# SEGplug.net
KiCad netlist of a schematic drawn in EAGLE
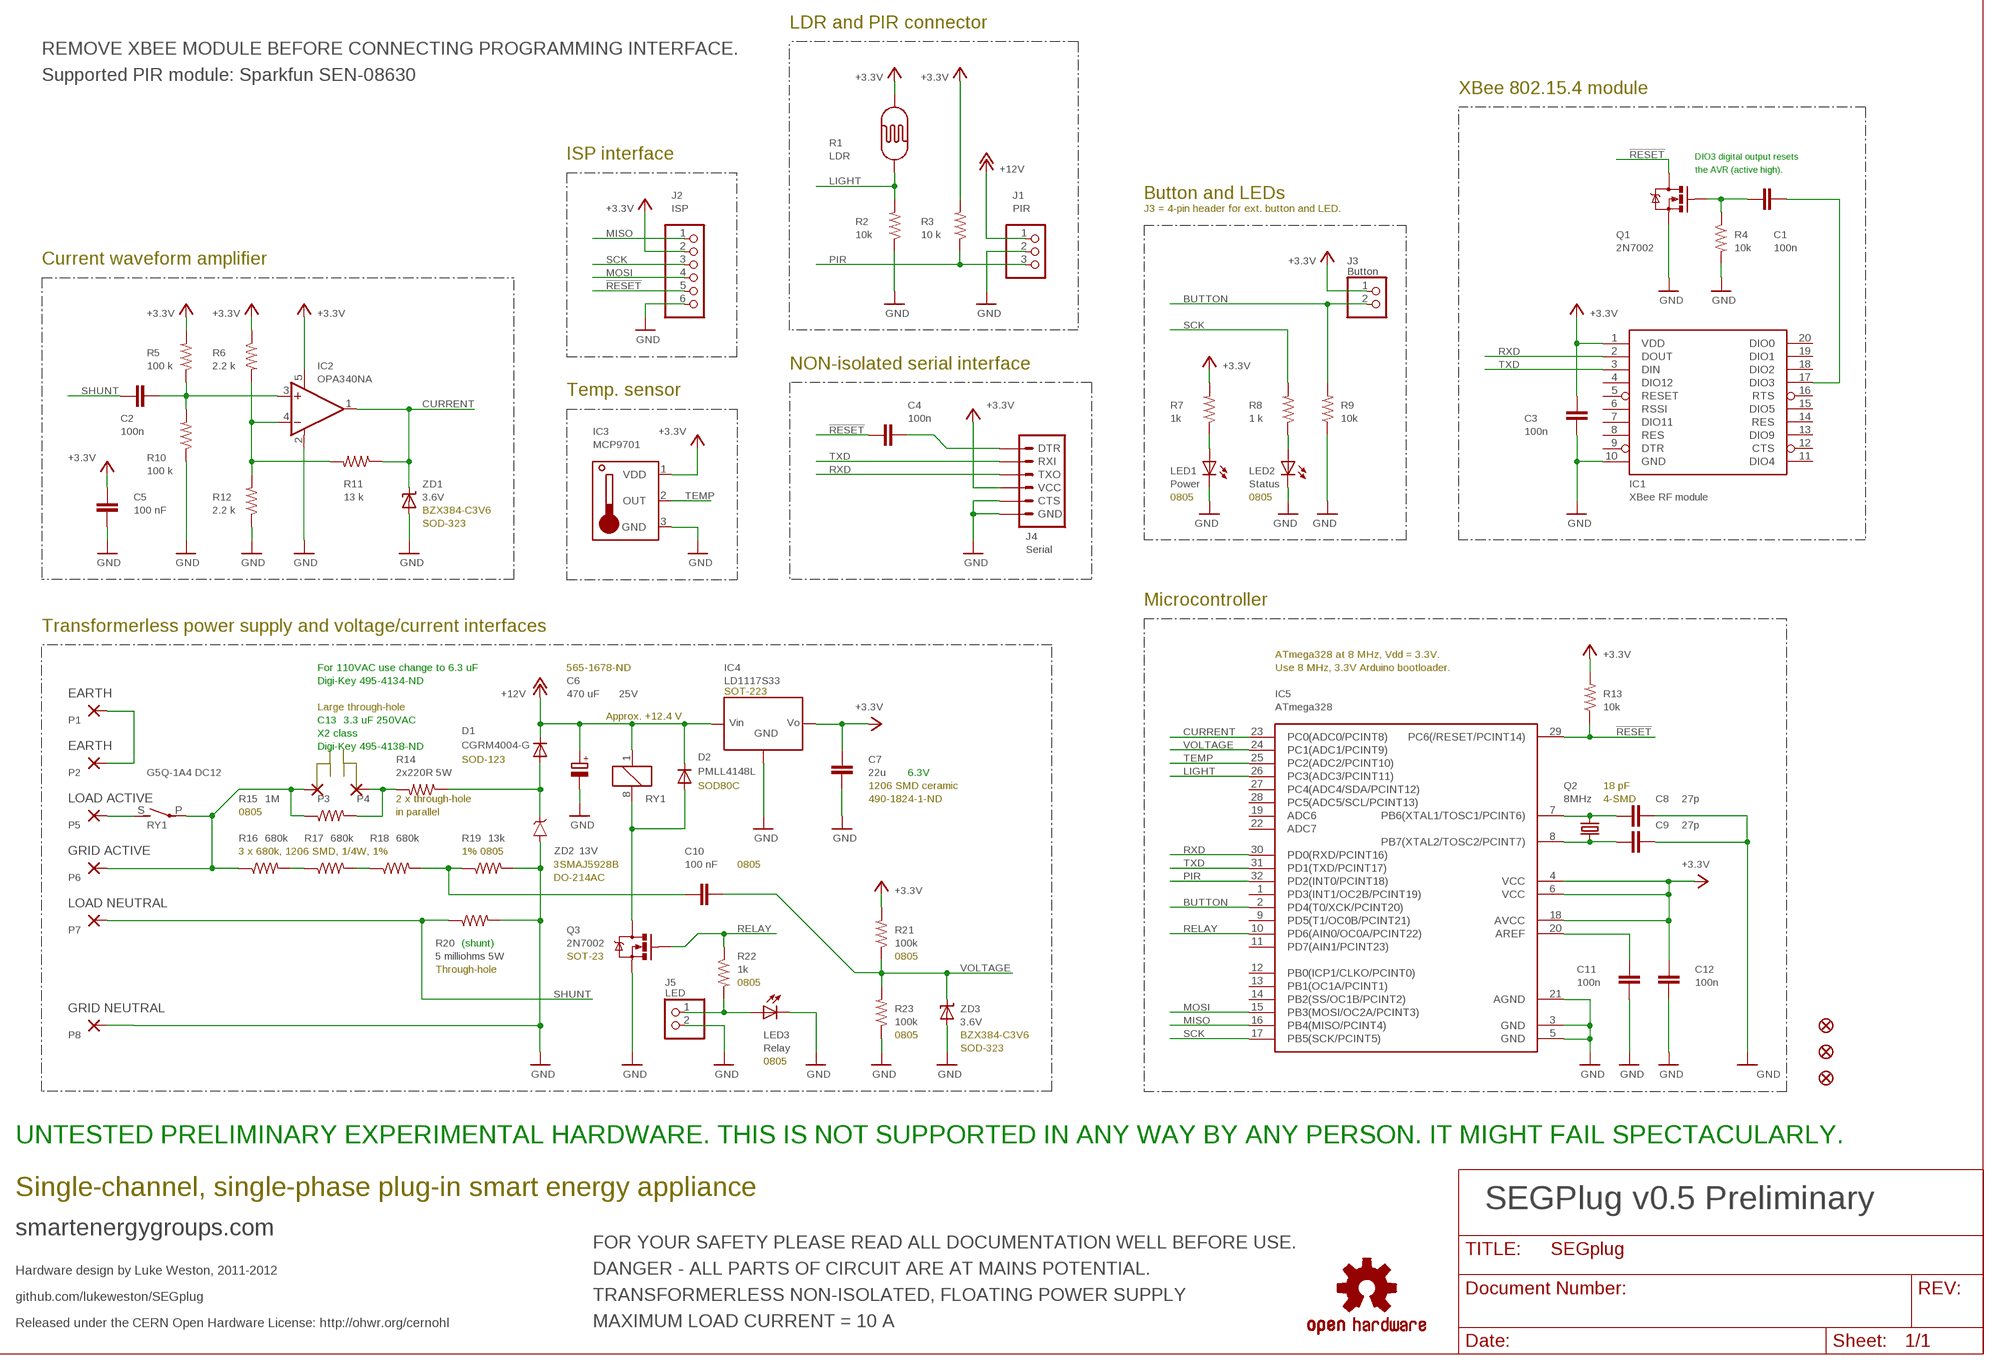
[diagram p0: schematic, sheet 1, part 1 of 2]
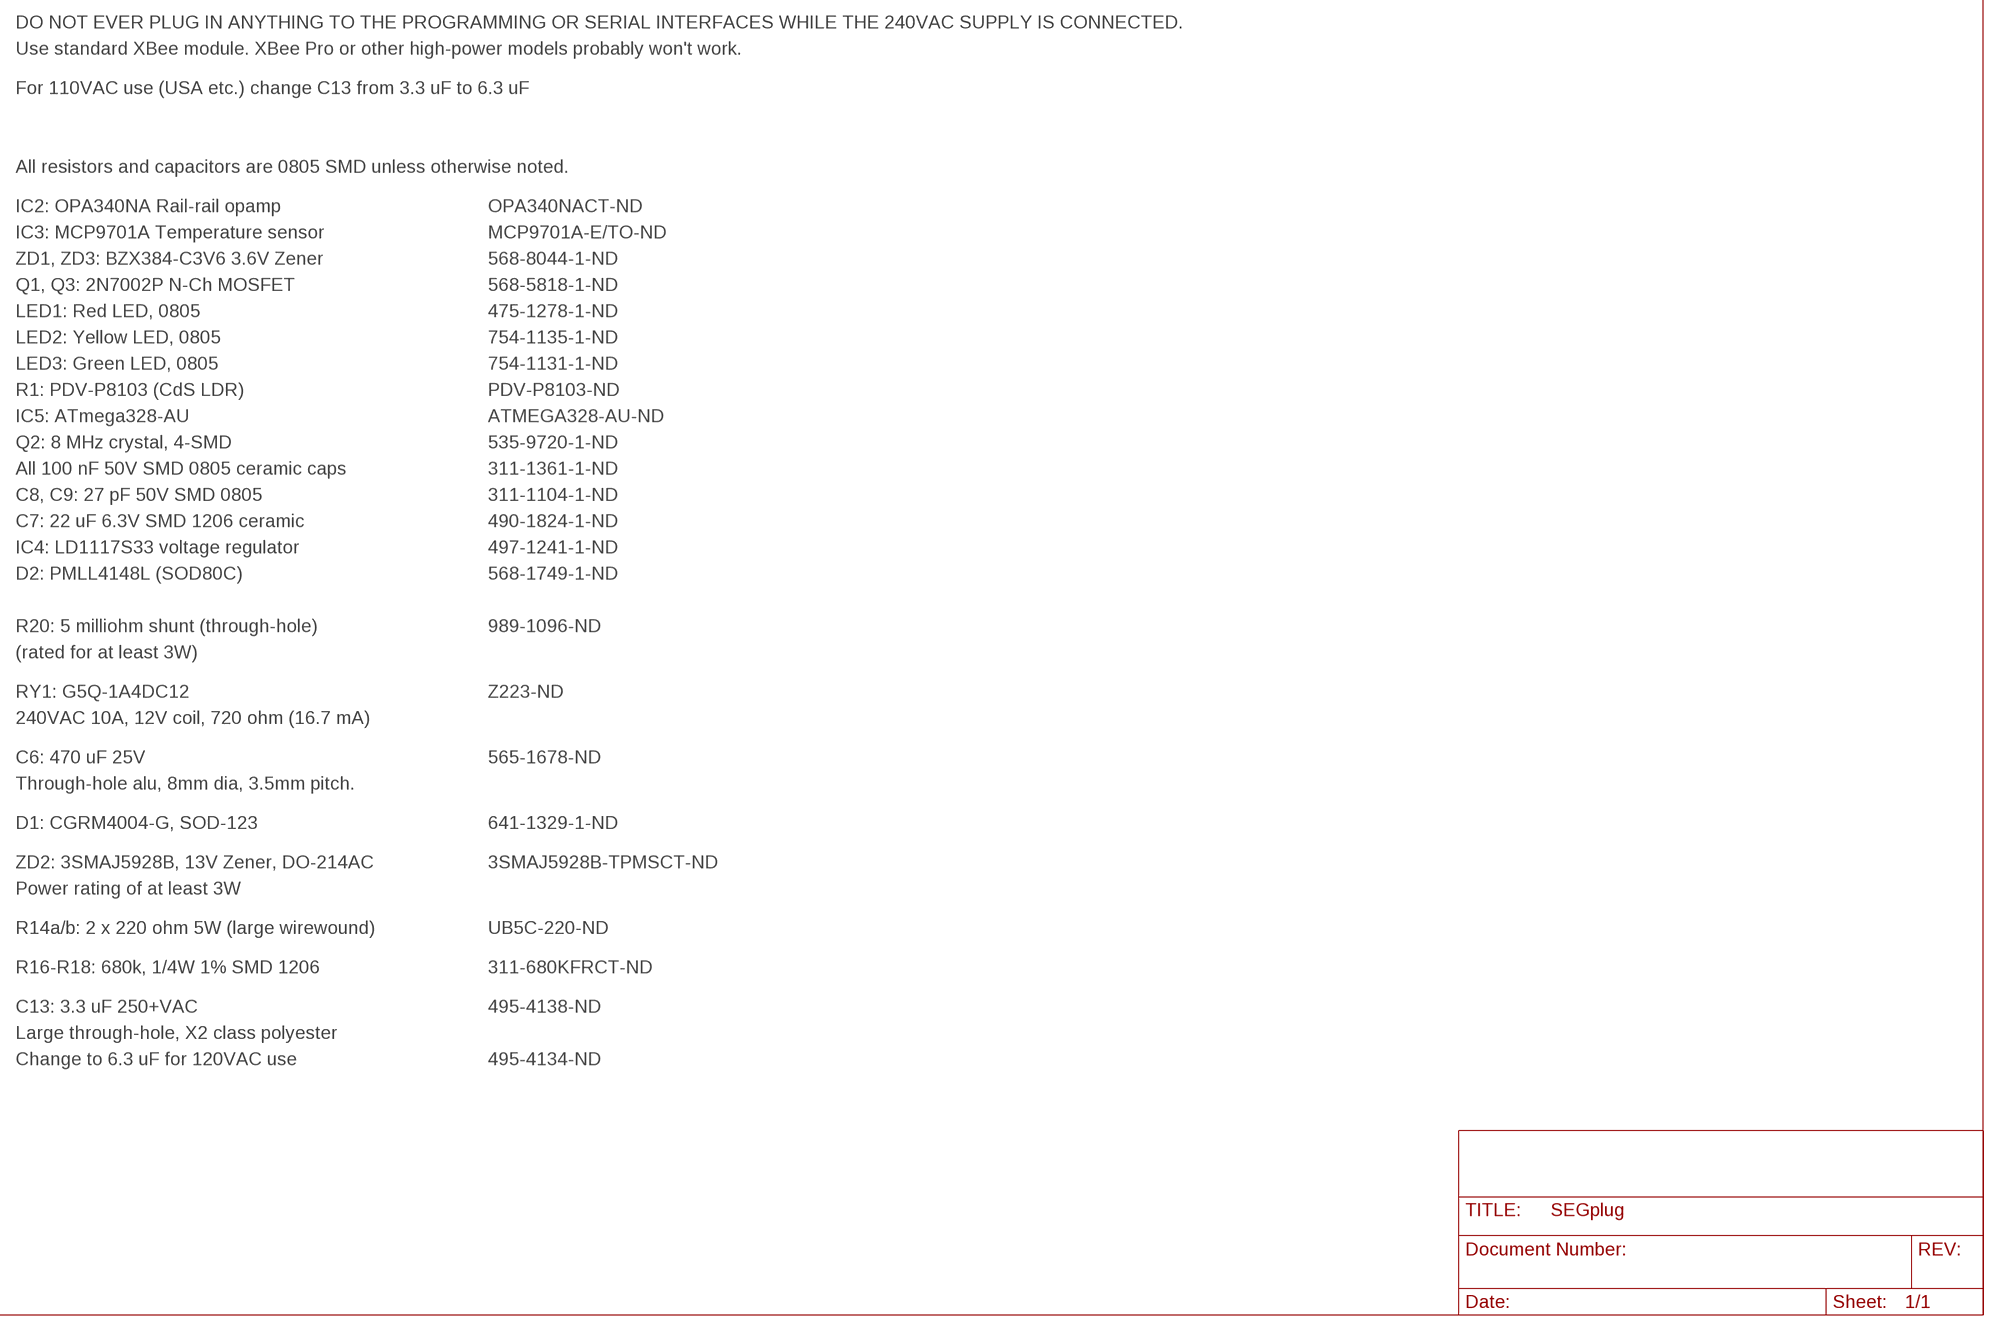
[diagram p1: schematic, sheet 1, part 2 of 2]

(export (version "E")
  (design (tool "Eeschema 10.0.6"))
  (components
    (comp (ref "C1")
      (value "100n")
      (footprint "eagle-import:C0805K")
      (libsource (lib "eagle-import") (part "C-EUC0805K"))
    )
    (comp (ref "C2")
      (value "100n")
      (footprint "eagle-import:C0805K")
      (libsource (lib "eagle-import") (part "C-EUC0805K"))
    )
    (comp (ref "C3")
      (value "100n")
      (footprint "eagle-import:C0805K")
      (libsource (lib "eagle-import") (part "C-EUC0805K"))
    )
    (comp (ref "C4")
      (value "100n")
      (footprint "eagle-import:C0805K")
      (libsource (lib "eagle-import") (part "C-EUC0805K"))
    )
    (comp (ref "C5")
      (value "100 nF")
      (footprint "eagle-import:C0805K")
      (libsource (lib "eagle-import") (part "C-EUC0805K"))
    )
    (comp (ref "C6")
      (value "470 uF")
      (footprint "eagle-import:E3,5-8")
      (libsource (lib "eagle-import") (part "CPOL-EUE3.5-8"))
    )
    (comp (ref "C7")
      (value "22u")
      (footprint "eagle-import:C1206K")
      (libsource (lib "eagle-import") (part "C-EUC1206K"))
    )
    (comp (ref "C8")
      (value "27p")
      (footprint "eagle-import:C0805K")
      (libsource (lib "eagle-import") (part "C-EUC0805K"))
    )
    (comp (ref "C9")
      (value "27p")
      (footprint "eagle-import:C0805K")
      (libsource (lib "eagle-import") (part "C-EUC0805K"))
    )
    (comp (ref "C10")
      (value "100 nF")
      (footprint "eagle-import:C0805K")
      (libsource (lib "eagle-import") (part "C-EUC0805K"))
    )
    (comp (ref "C11")
      (value "100n")
      (footprint "eagle-import:C0805K")
      (libsource (lib "eagle-import") (part "C-EUC0805K"))
    )
    (comp (ref "C12")
      (value "100n")
      (footprint "eagle-import:C0805K")
      (libsource (lib "eagle-import") (part "C-EUC0805K"))
    )
    (comp (ref "D1")
      (value "CGRM4004-G")
      (footprint "eagle-import:SOD-123_MINI-SMA")
      (libsource (lib "eagle-import") (part "CGRM400-G4"))
    )
    (comp (ref "D2")
      (value "PMLL4148L")
      (footprint "eagle-import:MINIMELF")
      (libsource (lib "eagle-import") (part "DIODE-MINIMELF"))
    )
    (comp (ref "IC1")
      (value "XBee RF module")
      (footprint "eagle-import:XBEE-SMD")
      (libsource (lib "eagle-import") (part "XBEE-1B3"))
    )
    (comp (ref "IC2")
      (value "OPA340NA")
      (footprint "eagle-import:SOT23-5")
      (fields (field (name "MPN") "OPA336NA"))
      (libsource (lib "eagle-import") (part "OPA336N"))
    )
    (comp (ref "IC3")
      (value "MCP9701")
      (footprint "eagle-import:TO92")
      (libsource (lib "eagle-import") (part "MCP9700"))
    )
    (comp (ref "IC4")
      (value "LD1117S33")
      (footprint "eagle-import:SOT223")
      (fields (field (name "MPN") "REG1117"))
      (libsource (lib "eagle-import") (part "REG1117"))
    )
    (comp (ref "IC5")
      (value "ATmega328")
      (footprint "eagle-import:TQFP32-08")
      (libsource (lib "eagle-import") (part "MEGA48/88/168-AU"))
    )
    (comp (ref "J1")
      (value "PIR")
      (footprint "eagle-import:1X03")
      (libsource (lib "eagle-import") (part "PINHD-1X3"))
    )
    (comp (ref "J2")
      (value "ISP")
      (footprint "eagle-import:1X06")
      (libsource (lib "eagle-import") (part "PINHD-1X6"))
    )
    (comp (ref "J3")
      (value "Button")
      (footprint "eagle-import:1X02")
      (libsource (lib "eagle-import") (part "PINHD-1X2"))
    )
    (comp (ref "J4")
      (value "Serial")
      (footprint "eagle-import:1X06")
      (libsource (lib "eagle-import") (part "ARDUINO_SERIAL_PROGRAMPTH"))
    )
    (comp (ref "J5")
      (value "LED")
      (footprint "eagle-import:1X02")
      (libsource (lib "eagle-import") (part "PINHD-1X2"))
    )
    (comp (ref "JP1")
      (value "FIDUCIAL1X2")
      (footprint "eagle-import:FIDUCIAL-1X2")
      (libsource (lib "eagle-import") (part "FIDUCIAL1X2"))
    )
    (comp (ref "JP2")
      (value "FIDUCIAL1X2")
      (footprint "eagle-import:FIDUCIAL-1X2")
      (libsource (lib "eagle-import") (part "FIDUCIAL1X2"))
    )
    (comp (ref "JP3")
      (value "FIDUCIAL1X2")
      (footprint "eagle-import:FIDUCIAL-1X2")
      (libsource (lib "eagle-import") (part "FIDUCIAL1X2"))
    )
    (comp (ref "LED1")
      (value "Power")
      (footprint "eagle-import:CHIPLED_0805")
      (libsource (lib "eagle-import") (part "LEDCHIPLED_0805"))
    )
    (comp (ref "LED2")
      (value "Status")
      (footprint "eagle-import:CHIPLED_0805")
      (libsource (lib "eagle-import") (part "LEDCHIPLED_0805"))
    )
    (comp (ref "LED3")
      (value "Relay")
      (footprint "eagle-import:CHIPLED_0805")
      (libsource (lib "eagle-import") (part "LEDCHIPLED_0805"))
    )
    (comp (ref "P1")
      (value "EARTH")
      (footprint "eagle-import:4,16O1,6")
      (libsource (lib "eagle-import") (part "WIREPAD4,16O1,6"))
    )
    (comp (ref "P2")
      (value "EARTH")
      (footprint "eagle-import:4,16O1,6")
      (libsource (lib "eagle-import") (part "WIREPAD4,16O1,6"))
    )
    (comp (ref "P3")
      (value "CAP")
      (footprint "eagle-import:4,16O1,6")
      (libsource (lib "eagle-import") (part "WIREPAD4,16O1,6"))
    )
    (comp (ref "P4")
      (value "CAP")
      (footprint "eagle-import:4,16O1,6")
      (libsource (lib "eagle-import") (part "WIREPAD4,16O1,6"))
    )
    (comp (ref "P5")
      (value "LOAD ACTIVE")
      (footprint "eagle-import:4,16O1,6")
      (libsource (lib "eagle-import") (part "WIREPAD4,16O1,6"))
    )
    (comp (ref "P6")
      (value "GRID ACTIVE")
      (footprint "eagle-import:4,16O1,6")
      (libsource (lib "eagle-import") (part "WIREPAD4,16O1,6"))
    )
    (comp (ref "P7")
      (value "LOAD NEUTRAL")
      (footprint "eagle-import:4,16O1,6")
      (libsource (lib "eagle-import") (part "WIREPAD4,16O1,6"))
    )
    (comp (ref "P8")
      (value "GRID NEUTRAL")
      (footprint "eagle-import:4,16O1,6")
      (libsource (lib "eagle-import") (part "WIREPAD4,16O1,6"))
    )
    (comp (ref "Q1")
      (value "2N7002")
      (footprint "eagle-import:SOT23-3")
      (libsource (lib "eagle-import") (part "MOSFET-NCHANNELSMD"))
    )
    (comp (ref "Q2")
      (value "8MHz")
      (footprint "eagle-import:CRYSTAL-SMD-5X3")
      (libsource (lib "eagle-import") (part "CRYSTAL5X3"))
    )
    (comp (ref "Q3")
      (value "2N7002")
      (footprint "eagle-import:SOT23-3")
      (libsource (lib "eagle-import") (part "MOSFET-NCHANNELSMD"))
    )
    (comp (ref "R1")
      (value "LDR")
      (footprint "eagle-import:PHOTOCELL")
      (libsource (lib "eagle-import") (part "PHOTOCELLPTH"))
    )
    (comp (ref "R2")
      (value "10k")
      (footprint "eagle-import:M0805")
      (libsource (lib "eagle-import") (part "resistor_R-US_M0805"))
    )
    (comp (ref "R3")
      (value "10 k")
      (footprint "eagle-import:M0805")
      (libsource (lib "eagle-import") (part "resistor_R-US_M0805"))
    )
    (comp (ref "R4")
      (value "10k")
      (footprint "eagle-import:M0805")
      (libsource (lib "eagle-import") (part "resistor_R-US_M0805"))
    )
    (comp (ref "R5")
      (value "100 k")
      (footprint "eagle-import:M0805")
      (libsource (lib "eagle-import") (part "resistor_R-US_M0805"))
    )
    (comp (ref "R6")
      (value "2.2 k")
      (footprint "eagle-import:M0805")
      (libsource (lib "eagle-import") (part "resistor_R-US_M0805"))
    )
    (comp (ref "R7")
      (value "1k")
      (footprint "eagle-import:M0805")
      (libsource (lib "eagle-import") (part "resistor_R-US_M0805"))
    )
    (comp (ref "R8")
      (value "1 k")
      (footprint "eagle-import:M0805")
      (libsource (lib "eagle-import") (part "resistor_R-US_M0805"))
    )
    (comp (ref "R9")
      (value "10k")
      (footprint "eagle-import:M0805")
      (libsource (lib "eagle-import") (part "resistor_R-US_M0805"))
    )
    (comp (ref "R10")
      (value "100 k")
      (footprint "eagle-import:M0805")
      (libsource (lib "eagle-import") (part "resistor_R-US_M0805"))
    )
    (comp (ref "R11")
      (value "13 k")
      (footprint "eagle-import:M0805")
      (libsource (lib "eagle-import") (part "resistor_R-US_M0805"))
    )
    (comp (ref "R12")
      (value "2.2 k")
      (footprint "eagle-import:M0805")
      (libsource (lib "eagle-import") (part "resistor_R-US_M0805"))
    )
    (comp (ref "R13")
      (value "10k")
      (footprint "eagle-import:M0805")
      (libsource (lib "eagle-import") (part "resistor_R-US_M0805"))
    )
    (comp (ref "R14")
      (value "2x220R 5W")
      (footprint "eagle-import:0617_17")
      (libsource (lib "eagle-import") (part "R-US_0617/17"))
    )
    (comp (ref "R15")
      (value "1M")
      (footprint "eagle-import:M0805")
      (libsource (lib "eagle-import") (part "R-US_M0805"))
    )
    (comp (ref "R16")
      (value "680k")
      (footprint "eagle-import:M1206")
      (libsource (lib "eagle-import") (part "R-US_M1206"))
    )
    (comp (ref "R17")
      (value "680k")
      (footprint "eagle-import:M1206")
      (libsource (lib "eagle-import") (part "R-US_M1206"))
    )
    (comp (ref "R18")
      (value "680k")
      (footprint "eagle-import:M1206")
      (libsource (lib "eagle-import") (part "R-US_M1206"))
    )
    (comp (ref "R19")
      (value "13k")
      (footprint "eagle-import:M0805")
      (libsource (lib "eagle-import") (part "resistor_R-US_M0805"))
    )
    (comp (ref "R20")
      (value "5 milliohms 5W")
      (footprint "eagle-import:RSENSE2_RSENSE")
      (libsource (lib "eagle-import") (part "RSENSE2_RSENSE"))
    )
    (comp (ref "R21")
      (value "100k")
      (footprint "eagle-import:M0805")
      (libsource (lib "eagle-import") (part "resistor_R-US_M0805"))
    )
    (comp (ref "R22")
      (value "1k")
      (footprint "eagle-import:M0805")
      (libsource (lib "eagle-import") (part "resistor_R-US_M0805"))
    )
    (comp (ref "R23")
      (value "100k")
      (footprint "eagle-import:M0805")
      (libsource (lib "eagle-import") (part "resistor_R-US_M0805"))
    )
    (comp (ref "RY1")
      (value "G5Q-1A4 DC12")
      (footprint "eagle-import:G6C-1117P")
      (libsource (lib "eagle-import") (part "G6C-1117P"))
    )
    (comp (ref "U$")
      (value "OSHW-LOGOS")
      (footprint "eagle-import:OSHW-LOGO-S")
      (libsource (lib "eagle-import") (part "OSHW-LOGOS"))
    )
    (comp (ref "ZD1")
      (value "3.6V")
      (footprint "eagle-import:SOD-323")
      (libsource (lib "eagle-import") (part "DIODE-ZENER-BZT52"))
    )
    (comp (ref "ZD2")
      (value "13V")
      (footprint "eagle-import:DO214AC")
      (libsource (lib "eagle-import") (part "ZENER"))
    )
    (comp (ref "ZD3")
      (value "3.6V")
      (footprint "eagle-import:SOD-323")
      (libsource (lib "eagle-import") (part "DIODE-ZENER-BZT52"))
    )
  )
  (nets
    (net (code "1") (name "+3.3V") (class "Default")
      (node (ref "C12") (pin "1") (pinfunction "1_1") (pintype "passive"))
      (node (ref "C3") (pin "1") (pinfunction "1_1") (pintype "passive"))
      (node (ref "C5") (pin "1") (pinfunction "1_1") (pintype "passive"))
      (node (ref "C7") (pin "1") (pinfunction "1_1") (pintype "passive"))
      (node (ref "IC1") (pin "1") (pinfunction "VDD_1") (pintype "power_in"))
      (node (ref "IC2") (pin "5") (pinfunction "V+_5") (pintype "power_in"))
      (node (ref "IC3") (pin "1") (pinfunction "VDD_1") (pintype "power_in"))
      (node (ref "IC4") (pin "2") (pinfunction "VOUT_2") (pintype "power_in"))
      (node (ref "IC5") (pin "18") (pinfunction "AVCC_18") (pintype "passive"))
      (node (ref "IC5") (pin "4") (pinfunction "VCC_4") (pintype "power_in"))
      (node (ref "IC5") (pin "6") (pinfunction "VCC_6") (pintype "power_in"))
      (node (ref "J2") (pin "2") (pinfunction "2_2") (pintype "passive"))
      (node (ref "J3") (pin "1") (pinfunction "1_1") (pintype "passive"))
      (node (ref "J4") (pin "4") (pinfunction "VCC_4") (pintype "passive"))
      (node (ref "R1") (pin "2") (pinfunction "P$2_2") (pintype "bidirectional"))
      (node (ref "R13") (pin "2") (pinfunction "2_2") (pintype "passive"))
      (node (ref "R21") (pin "2") (pinfunction "2_2") (pintype "passive"))
      (node (ref "R3") (pin "2") (pinfunction "2_2") (pintype "passive"))
      (node (ref "R5") (pin "2") (pinfunction "2_2") (pintype "passive"))
      (node (ref "R6") (pin "1") (pinfunction "1_1") (pintype "passive"))
      (node (ref "R7") (pin "2") (pinfunction "2_2") (pintype "passive"))
    )
    (net (code "2") (name "+12V") (class "Default")
      (node (ref "C6") (pin "+") (pinfunction "+_+") (pintype "passive"))
      (node (ref "D1") (pin "C") (pinfunction "C_C") (pintype "passive"))
      (node (ref "D2") (pin "C") (pinfunction "C_C") (pintype "passive"))
      (node (ref "IC4") (pin "3") (pinfunction "VIN_3") (pintype "power_in"))
      (node (ref "J1") (pin "1") (pinfunction "1_1") (pintype "passive"))
      (node (ref "RY1") (pin "1") (pinfunction "1_1") (pintype "passive"))
    )
    (net (code "3") (name "/BUTTON") (class "Default")
      (node (ref "IC5") (pin "2") (pinfunction "PD4(T0/XCK/PCINT20)_2") (pintype "bidirectional"))
      (node (ref "J3") (pin "2") (pinfunction "2_2") (pintype "passive"))
      (node (ref "R9") (pin "2") (pinfunction "2_2") (pintype "passive"))
    )
    (net (code "4") (name "/CURRENT") (class "Default")
      (node (ref "IC2") (pin "1") (pinfunction "OUT_1") (pintype "output"))
      (node (ref "IC5") (pin "23") (pinfunction "PC0(ADC0/PCINT8)_23") (pintype "bidirectional"))
      (node (ref "R11") (pin "1") (pinfunction "1_1") (pintype "passive"))
      (node (ref "ZD1") (pin "1") (pinfunction "C_1") (pintype "passive"))
    )
    (net (code "5") (name "/LIGHT") (class "Default")
      (node (ref "IC5") (pin "26") (pinfunction "PC3(ADC3/PCINT11)_26") (pintype "bidirectional"))
      (node (ref "R1") (pin "1") (pinfunction "P$1_1") (pintype "bidirectional"))
      (node (ref "R2") (pin "2") (pinfunction "2_2") (pintype "passive"))
    )
    (net (code "6") (name "/MISO") (class "Default")
      (node (ref "IC5") (pin "16") (pinfunction "PB4(MISO/PCINT4)_16") (pintype "bidirectional"))
      (node (ref "J2") (pin "1") (pinfunction "1_1") (pintype "passive"))
    )
    (net (code "7") (name "/MOSI") (class "Default")
      (node (ref "IC5") (pin "15") (pinfunction "PB3(MOSI/OC2A/PCINT3)_15") (pintype "bidirectional"))
      (node (ref "J2") (pin "4") (pinfunction "4_4") (pintype "passive"))
    )
    (net (code "8") (name "/PIR") (class "Default")
      (node (ref "IC5") (pin "32") (pinfunction "PD2(INT0/PCINT18)_32") (pintype "bidirectional"))
      (node (ref "J1") (pin "3") (pinfunction "3_3") (pintype "passive"))
      (node (ref "R3") (pin "1") (pinfunction "1_1") (pintype "passive"))
    )
    (net (code "9") (name "/RELAY") (class "Default")
      (node (ref "IC5") (pin "10") (pinfunction "PD6(AIN0/OC0A/PCINT22)_10") (pintype "bidirectional"))
      (node (ref "Q3") (pin "1") (pinfunction "G_1") (pintype "passive"))
      (node (ref "R22") (pin "1") (pinfunction "1_1") (pintype "passive"))
    )
    (net (code "10") (name "/RXD") (class "Default")
      (node (ref "IC1") (pin "2") (pinfunction "DOUT_2") (pintype "output"))
      (node (ref "IC5") (pin "30") (pinfunction "PD0(RXD/PCINT16)_30") (pintype "bidirectional"))
      (node (ref "J4") (pin "3") (pinfunction "TXO_3") (pintype "passive"))
    )
    (net (code "11") (name "/SCK") (class "Default")
      (node (ref "IC5") (pin "17") (pinfunction "PB5(SCK/PCINT5)_17") (pintype "bidirectional"))
      (node (ref "J2") (pin "3") (pinfunction "3_3") (pintype "passive"))
      (node (ref "R8") (pin "2") (pinfunction "2_2") (pintype "passive"))
    )
    (net (code "12") (name "/SHUNT") (class "Default")
      (node (ref "C2") (pin "2") (pinfunction "2_2") (pintype "passive"))
      (node (ref "P7") (pin "1") (pinfunction "P_1") (pintype "passive"))
      (node (ref "R20") (pin "P$1") (pinfunction "1_P$1") (pintype "passive"))
    )
    (net (code "13") (name "/TEMP") (class "Default")
      (node (ref "IC3") (pin "2") (pinfunction "OUT_2") (pintype "output"))
      (node (ref "IC5") (pin "25") (pinfunction "PC2(ADC2/PCINT10)_25") (pintype "bidirectional"))
    )
    (net (code "14") (name "/TXD") (class "Default")
      (node (ref "IC1") (pin "3") (pinfunction "DIN_3") (pintype "input"))
      (node (ref "IC5") (pin "31") (pinfunction "PD1(TXD/PCINT17)_31") (pintype "bidirectional"))
      (node (ref "J4") (pin "2") (pinfunction "RXI_2") (pintype "passive"))
    )
    (net (code "15") (name "/VOLTAGE") (class "Default")
      (node (ref "C10") (pin "1") (pinfunction "1_1") (pintype "passive"))
      (node (ref "IC5") (pin "24") (pinfunction "PC1(ADC1/PCINT9)_24") (pintype "bidirectional"))
      (node (ref "R21") (pin "1") (pinfunction "1_1") (pintype "passive"))
      (node (ref "R23") (pin "2") (pinfunction "2_2") (pintype "passive"))
      (node (ref "ZD3") (pin "1") (pinfunction "C_1") (pintype "passive"))
    )
    (net (code "16") (name "/~{RESET}") (class "Default")
      (node (ref "C4") (pin "2") (pinfunction "2_2") (pintype "passive"))
      (node (ref "IC5") (pin "29") (pinfunction "PC6(/RESET/PCINT14)_29") (pintype "bidirectional"))
      (node (ref "J2") (pin "5") (pinfunction "5_5") (pintype "passive"))
      (node (ref "Q1") (pin "3") (pinfunction "D_3") (pintype "passive"))
      (node (ref "R13") (pin "1") (pinfunction "1_1") (pintype "passive"))
    )
    (net (code "17") (name "GND") (class "Default")
      (node (ref "C11") (pin "2") (pinfunction "2_2") (pintype "passive"))
      (node (ref "C12") (pin "2") (pinfunction "2_2") (pintype "passive"))
      (node (ref "C3") (pin "2") (pinfunction "2_2") (pintype "passive"))
      (node (ref "C5") (pin "2") (pinfunction "2_2") (pintype "passive"))
      (node (ref "C6") (pin "-") (pinfunction "-_-") (pintype "passive"))
      (node (ref "C7") (pin "2") (pinfunction "2_2") (pintype "passive"))
      (node (ref "C8") (pin "2") (pinfunction "2_2") (pintype "passive"))
      (node (ref "C9") (pin "2") (pinfunction "2_2") (pintype "passive"))
      (node (ref "IC1") (pin "10") (pinfunction "GND_10") (pintype "power_in"))
      (node (ref "IC2") (pin "2") (pinfunction "V-_2") (pintype "power_in"))
      (node (ref "IC3") (pin "3") (pinfunction "GND_3") (pintype "power_in"))
      (node (ref "IC4") (pin "1") (pinfunction "GND_1") (pintype "power_in"))
      (node (ref "IC5") (pin "21") (pinfunction "AGND_21") (pintype "power_in"))
      (node (ref "IC5") (pin "3") (pinfunction "GND_3") (pintype "power_in"))
      (node (ref "IC5") (pin "5") (pinfunction "GND_5") (pintype "power_in"))
      (node (ref "J1") (pin "2") (pinfunction "2_2") (pintype "passive"))
      (node (ref "J2") (pin "6") (pinfunction "6_6") (pintype "passive"))
      (node (ref "J4") (pin "5") (pinfunction "CTS_5") (pintype "passive"))
      (node (ref "J4") (pin "6") (pinfunction "GND_6") (pintype "passive"))
      (node (ref "J5") (pin "2") (pinfunction "2_2") (pintype "passive"))
      (node (ref "LED1") (pin "C") (pinfunction "C_C") (pintype "passive"))
      (node (ref "LED2") (pin "C") (pinfunction "C_C") (pintype "passive"))
      (node (ref "LED3") (pin "C") (pinfunction "C_C") (pintype "passive"))
      (node (ref "P8") (pin "1") (pinfunction "P_1") (pintype "passive"))
      (node (ref "Q1") (pin "2") (pinfunction "S_2") (pintype "passive"))
      (node (ref "Q3") (pin "2") (pinfunction "S_2") (pintype "passive"))
      (node (ref "R10") (pin "1") (pinfunction "1_1") (pintype "passive"))
      (node (ref "R12") (pin "1") (pinfunction "1_1") (pintype "passive"))
      (node (ref "R19") (pin "2") (pinfunction "2_2") (pintype "passive"))
      (node (ref "R2") (pin "1") (pinfunction "1_1") (pintype "passive"))
      (node (ref "R20") (pin "P$2") (pinfunction "2_P$2") (pintype "passive"))
      (node (ref "R23") (pin "1") (pinfunction "1_1") (pintype "passive"))
      (node (ref "R4") (pin "2") (pinfunction "2_2") (pintype "passive"))
      (node (ref "R9") (pin "1") (pinfunction "1_1") (pintype "passive"))
      (node (ref "ZD1") (pin "2") (pinfunction "A_2") (pintype "passive"))
      (node (ref "ZD2") (pin "A") (pinfunction "A_A") (pintype "passive"))
      (node (ref "ZD3") (pin "2") (pinfunction "A_2") (pintype "passive"))
    )
    (net (code "18") (name "Net-(C10-Pad2)") (class "Default")
      (node (ref "C10") (pin "2") (pinfunction "2_2") (pintype "passive"))
      (node (ref "R18") (pin "2") (pinfunction "2_2") (pintype "passive"))
      (node (ref "R19") (pin "1") (pinfunction "1_1") (pintype "passive"))
    )
    (net (code "19") (name "Net-(D1-PadA)") (class "Default")
      (node (ref "D1") (pin "A") (pinfunction "A_A") (pintype "passive"))
      (node (ref "R14") (pin "1") (pinfunction "1_1") (pintype "passive"))
      (node (ref "ZD2") (pin "C") (pinfunction "C_C") (pintype "passive"))
    )
    (net (code "20") (name "Net-(IC1-DIO3)") (class "Default")
      (node (ref "C1") (pin "1") (pinfunction "1_1") (pintype "passive"))
      (node (ref "IC1") (pin "17") (pinfunction "DIO3_17") (pintype "bidirectional"))
    )
    (net (code "21") (name "Net-(IC2-+IN)") (class "Default")
      (node (ref "C2") (pin "1") (pinfunction "1_1") (pintype "passive"))
      (node (ref "IC2") (pin "3") (pinfunction "+IN_3") (pintype "input"))
      (node (ref "R10") (pin "2") (pinfunction "2_2") (pintype "passive"))
      (node (ref "R5") (pin "1") (pinfunction "1_1") (pintype "passive"))
    )
    (net (code "22") (name "Net-(IC2--IN)") (class "Default")
      (node (ref "IC2") (pin "4") (pinfunction "-IN_4") (pintype "input"))
      (node (ref "R11") (pin "2") (pinfunction "2_2") (pintype "passive"))
      (node (ref "R12") (pin "2") (pinfunction "2_2") (pintype "passive"))
      (node (ref "R6") (pin "2") (pinfunction "2_2") (pintype "passive"))
    )
    (net (code "23") (name "Net-(IC5-AREF)") (class "Default")
      (node (ref "C11") (pin "1") (pinfunction "1_1") (pintype "passive"))
      (node (ref "IC5") (pin "20") (pinfunction "AREF_20") (pintype "passive"))
    )
    (net (code "24") (name "Net-(IC5-PB6(XTAL1{slash}TOSC1{slash}PCINT6))") (class "Default")
      (node (ref "C8") (pin "1") (pinfunction "1_1") (pintype "passive"))
      (node (ref "IC5") (pin "7") (pinfunction "PB6(XTAL1/TOSC1/PCINT6)_7") (pintype "bidirectional"))
      (node (ref "Q2") (pin "3") (pinfunction "2_3") (pintype "passive"))
    )
    (net (code "25") (name "Net-(IC5-PB7(XTAL2{slash}TOSC2{slash}PCINT7))") (class "Default")
      (node (ref "C9") (pin "1") (pinfunction "1_1") (pintype "passive"))
      (node (ref "IC5") (pin "8") (pinfunction "PB7(XTAL2/TOSC2/PCINT7)_8") (pintype "bidirectional"))
      (node (ref "Q2") (pin "1") (pinfunction "1_1") (pintype "passive"))
    )
    (net (code "26") (name "Net-(J4-DTR)") (class "Default")
      (node (ref "C4") (pin "1") (pinfunction "1_1") (pintype "passive"))
      (node (ref "J4") (pin "1") (pinfunction "DTR_1") (pintype "passive"))
    )
    (net (code "27") (name "Net-(J5-Pad1)") (class "Default")
      (node (ref "J5") (pin "1") (pinfunction "1_1") (pintype "passive"))
      (node (ref "LED3") (pin "A") (pinfunction "A_A") (pintype "passive"))
      (node (ref "R22") (pin "2") (pinfunction "2_2") (pintype "passive"))
    )
    (net (code "28") (name "Net-(LED1-PadA)") (class "Default")
      (node (ref "LED1") (pin "A") (pinfunction "A_A") (pintype "passive"))
      (node (ref "R7") (pin "1") (pinfunction "1_1") (pintype "passive"))
    )
    (net (code "29") (name "Net-(LED2-PadA)") (class "Default")
      (node (ref "LED2") (pin "A") (pinfunction "A_A") (pintype "passive"))
      (node (ref "R8") (pin "1") (pinfunction "1_1") (pintype "passive"))
    )
    (net (code "30") (name "Net-(P1-P)") (class "Default")
      (node (ref "P1") (pin "1") (pinfunction "P_1") (pintype "passive"))
      (node (ref "P2") (pin "1") (pinfunction "P_1") (pintype "passive"))
    )
    (net (code "31") (name "Net-(P3-P)") (class "Default")
      (node (ref "P3") (pin "1") (pinfunction "P_1") (pintype "passive"))
      (node (ref "P6") (pin "1") (pinfunction "P_1") (pintype "passive"))
      (node (ref "R15") (pin "1") (pinfunction "1_1") (pintype "passive"))
      (node (ref "R16") (pin "1") (pinfunction "1_1") (pintype "passive"))
      (node (ref "RY1") (pin "P") (pinfunction "P_P") (pintype "passive"))
    )
    (net (code "32") (name "Net-(P4-P)") (class "Default")
      (node (ref "P4") (pin "1") (pinfunction "P_1") (pintype "passive"))
      (node (ref "R14") (pin "2") (pinfunction "2_2") (pintype "passive"))
      (node (ref "R15") (pin "2") (pinfunction "2_2") (pintype "passive"))
    )
    (net (code "33") (name "Net-(P5-P)") (class "Default")
      (node (ref "P5") (pin "1") (pinfunction "P_1") (pintype "passive"))
      (node (ref "RY1") (pin "S") (pinfunction "S_S") (pintype "passive"))
    )
    (net (code "34") (name "Net-(Q1-G)") (class "Default")
      (node (ref "C1") (pin "2") (pinfunction "2_2") (pintype "passive"))
      (node (ref "Q1") (pin "1") (pinfunction "G_1") (pintype "passive"))
      (node (ref "R4") (pin "1") (pinfunction "1_1") (pintype "passive"))
    )
    (net (code "35") (name "Net-(Q3-D)") (class "Default")
      (node (ref "D2") (pin "A") (pinfunction "A_A") (pintype "passive"))
      (node (ref "Q3") (pin "3") (pinfunction "D_3") (pintype "passive"))
      (node (ref "RY1") (pin "8") (pinfunction "2_8") (pintype "passive"))
    )
    (net (code "36") (name "Net-(R16-Pad2)") (class "Default")
      (node (ref "R16") (pin "2") (pinfunction "2_2") (pintype "passive"))
      (node (ref "R17") (pin "1") (pinfunction "1_1") (pintype "passive"))
    )
    (net (code "37") (name "Net-(R17-Pad2)") (class "Default")
      (node (ref "R17") (pin "2") (pinfunction "2_2") (pintype "passive"))
      (node (ref "R18") (pin "1") (pinfunction "1_1") (pintype "passive"))
    )
    (net (code "38") (name "unconnected-(IC1-CTS-Pad12)") (class "Default")
      (node (ref "IC1") (pin "12") (pinfunction "CTS_12") (pintype "output"))
    )
    (net (code "39") (name "unconnected-(IC1-DIO0-Pad20)") (class "Default")
      (node (ref "IC1") (pin "20") (pinfunction "DIO0_20") (pintype "bidirectional"))
    )
    (net (code "40") (name "unconnected-(IC1-DIO1-Pad19)") (class "Default")
      (node (ref "IC1") (pin "19") (pinfunction "DIO1_19") (pintype "bidirectional"))
    )
    (net (code "41") (name "unconnected-(IC1-DIO2-Pad18)") (class "Default")
      (node (ref "IC1") (pin "18") (pinfunction "DIO2_18") (pintype "bidirectional"))
    )
    (net (code "42") (name "unconnected-(IC1-DIO4-Pad11)") (class "Default")
      (node (ref "IC1") (pin "11") (pinfunction "DIO4_11") (pintype "bidirectional"))
    )
    (net (code "43") (name "unconnected-(IC1-DIO5-Pad15)") (class "Default")
      (node (ref "IC1") (pin "15") (pinfunction "DIO5_15") (pintype "bidirectional"))
    )
    (net (code "44") (name "unconnected-(IC1-DIO9-Pad13)") (class "Default")
      (node (ref "IC1") (pin "13") (pinfunction "DIO9_13") (pintype "bidirectional"))
    )
    (net (code "45") (name "unconnected-(IC1-DIO11-Pad7)") (class "Default")
      (node (ref "IC1") (pin "7") (pinfunction "DIO11_7") (pintype "bidirectional"))
    )
    (net (code "46") (name "unconnected-(IC1-DIO12-Pad4)") (class "Default")
      (node (ref "IC1") (pin "4") (pinfunction "DIO12_4") (pintype "bidirectional"))
    )
    (net (code "47") (name "unconnected-(IC1-DTR-Pad9)") (class "Default")
      (node (ref "IC1") (pin "9") (pinfunction "DTR_9") (pintype "bidirectional"))
    )
    (net (code "48") (name "unconnected-(IC1-RES-Pad8)") (class "Default")
      (node (ref "IC1") (pin "8") (pinfunction "RES_8") (pintype "bidirectional"))
    )
    (net (code "49") (name "unconnected-(IC1-RES-Pad14)") (class "Default")
      (node (ref "IC1") (pin "14") (pinfunction "RES_14") (pintype "bidirectional"))
    )
    (net (code "50") (name "unconnected-(IC1-RESET-Pad5)") (class "Default")
      (node (ref "IC1") (pin "5") (pinfunction "RESET_5") (pintype "input"))
    )
    (net (code "51") (name "unconnected-(IC1-RSSI-Pad6)") (class "Default")
      (node (ref "IC1") (pin "6") (pinfunction "RSSI_6") (pintype "bidirectional"))
    )
    (net (code "52") (name "unconnected-(IC1-RTS-Pad16)") (class "Default")
      (node (ref "IC1") (pin "16") (pinfunction "RTS_16") (pintype "input"))
    )
    (net (code "53") (name "unconnected-(IC5-ADC6-Pad19)") (class "Default")
      (node (ref "IC5") (pin "19") (pinfunction "ADC6_19") (pintype "passive"))
    )
    (net (code "54") (name "unconnected-(IC5-ADC7-Pad22)") (class "Default")
      (node (ref "IC5") (pin "22") (pinfunction "ADC7_22") (pintype "passive"))
    )
    (net (code "55") (name "unconnected-(IC5-PB0(ICP1{slash}CLKO{slash}PCINT0)-Pad12)") (class "Default")
      (node (ref "IC5") (pin "12") (pinfunction "PB0(ICP1/CLKO/PCINT0)_12") (pintype "bidirectional"))
    )
    (net (code "56") (name "unconnected-(IC5-PB1(OC1A{slash}PCINT1)-Pad13)") (class "Default")
      (node (ref "IC5") (pin "13") (pinfunction "PB1(OC1A/PCINT1)_13") (pintype "bidirectional"))
    )
    (net (code "57") (name "unconnected-(IC5-PB2(SS{slash}OC1B{slash}PCINT2)-Pad14)") (class "Default")
      (node (ref "IC5") (pin "14") (pinfunction "PB2(SS/OC1B/PCINT2)_14") (pintype "bidirectional"))
    )
    (net (code "58") (name "unconnected-(IC5-PC4(ADC4{slash}SDA{slash}PCINT12)-Pad27)") (class "Default")
      (node (ref "IC5") (pin "27") (pinfunction "PC4(ADC4/SDA/PCINT12)_27") (pintype "bidirectional"))
    )
    (net (code "59") (name "unconnected-(IC5-PC5(ADC5{slash}SCL{slash}PCINT13)-Pad28)") (class "Default")
      (node (ref "IC5") (pin "28") (pinfunction "PC5(ADC5/SCL/PCINT13)_28") (pintype "bidirectional"))
    )
    (net (code "60") (name "unconnected-(IC5-PD3(INT1{slash}OC2B{slash}PCINT19)-Pad1)") (class "Default")
      (node (ref "IC5") (pin "1") (pinfunction "PD3(INT1/OC2B/PCINT19)_1") (pintype "bidirectional"))
    )
    (net (code "61") (name "unconnected-(IC5-PD5(T1{slash}OC0B{slash}PCINT21)-Pad9)") (class "Default")
      (node (ref "IC5") (pin "9") (pinfunction "PD5(T1/OC0B/PCINT21)_9") (pintype "bidirectional"))
    )
    (net (code "62") (name "unconnected-(IC5-PD7(AIN1{slash}PCINT23)-Pad11)") (class "Default")
      (node (ref "IC5") (pin "11") (pinfunction "PD7(AIN1/PCINT23)_11") (pintype "bidirectional"))
    )
  )
)
